# Mega_setup.net
KiCad netlist of a schematic drawn in EAGLE
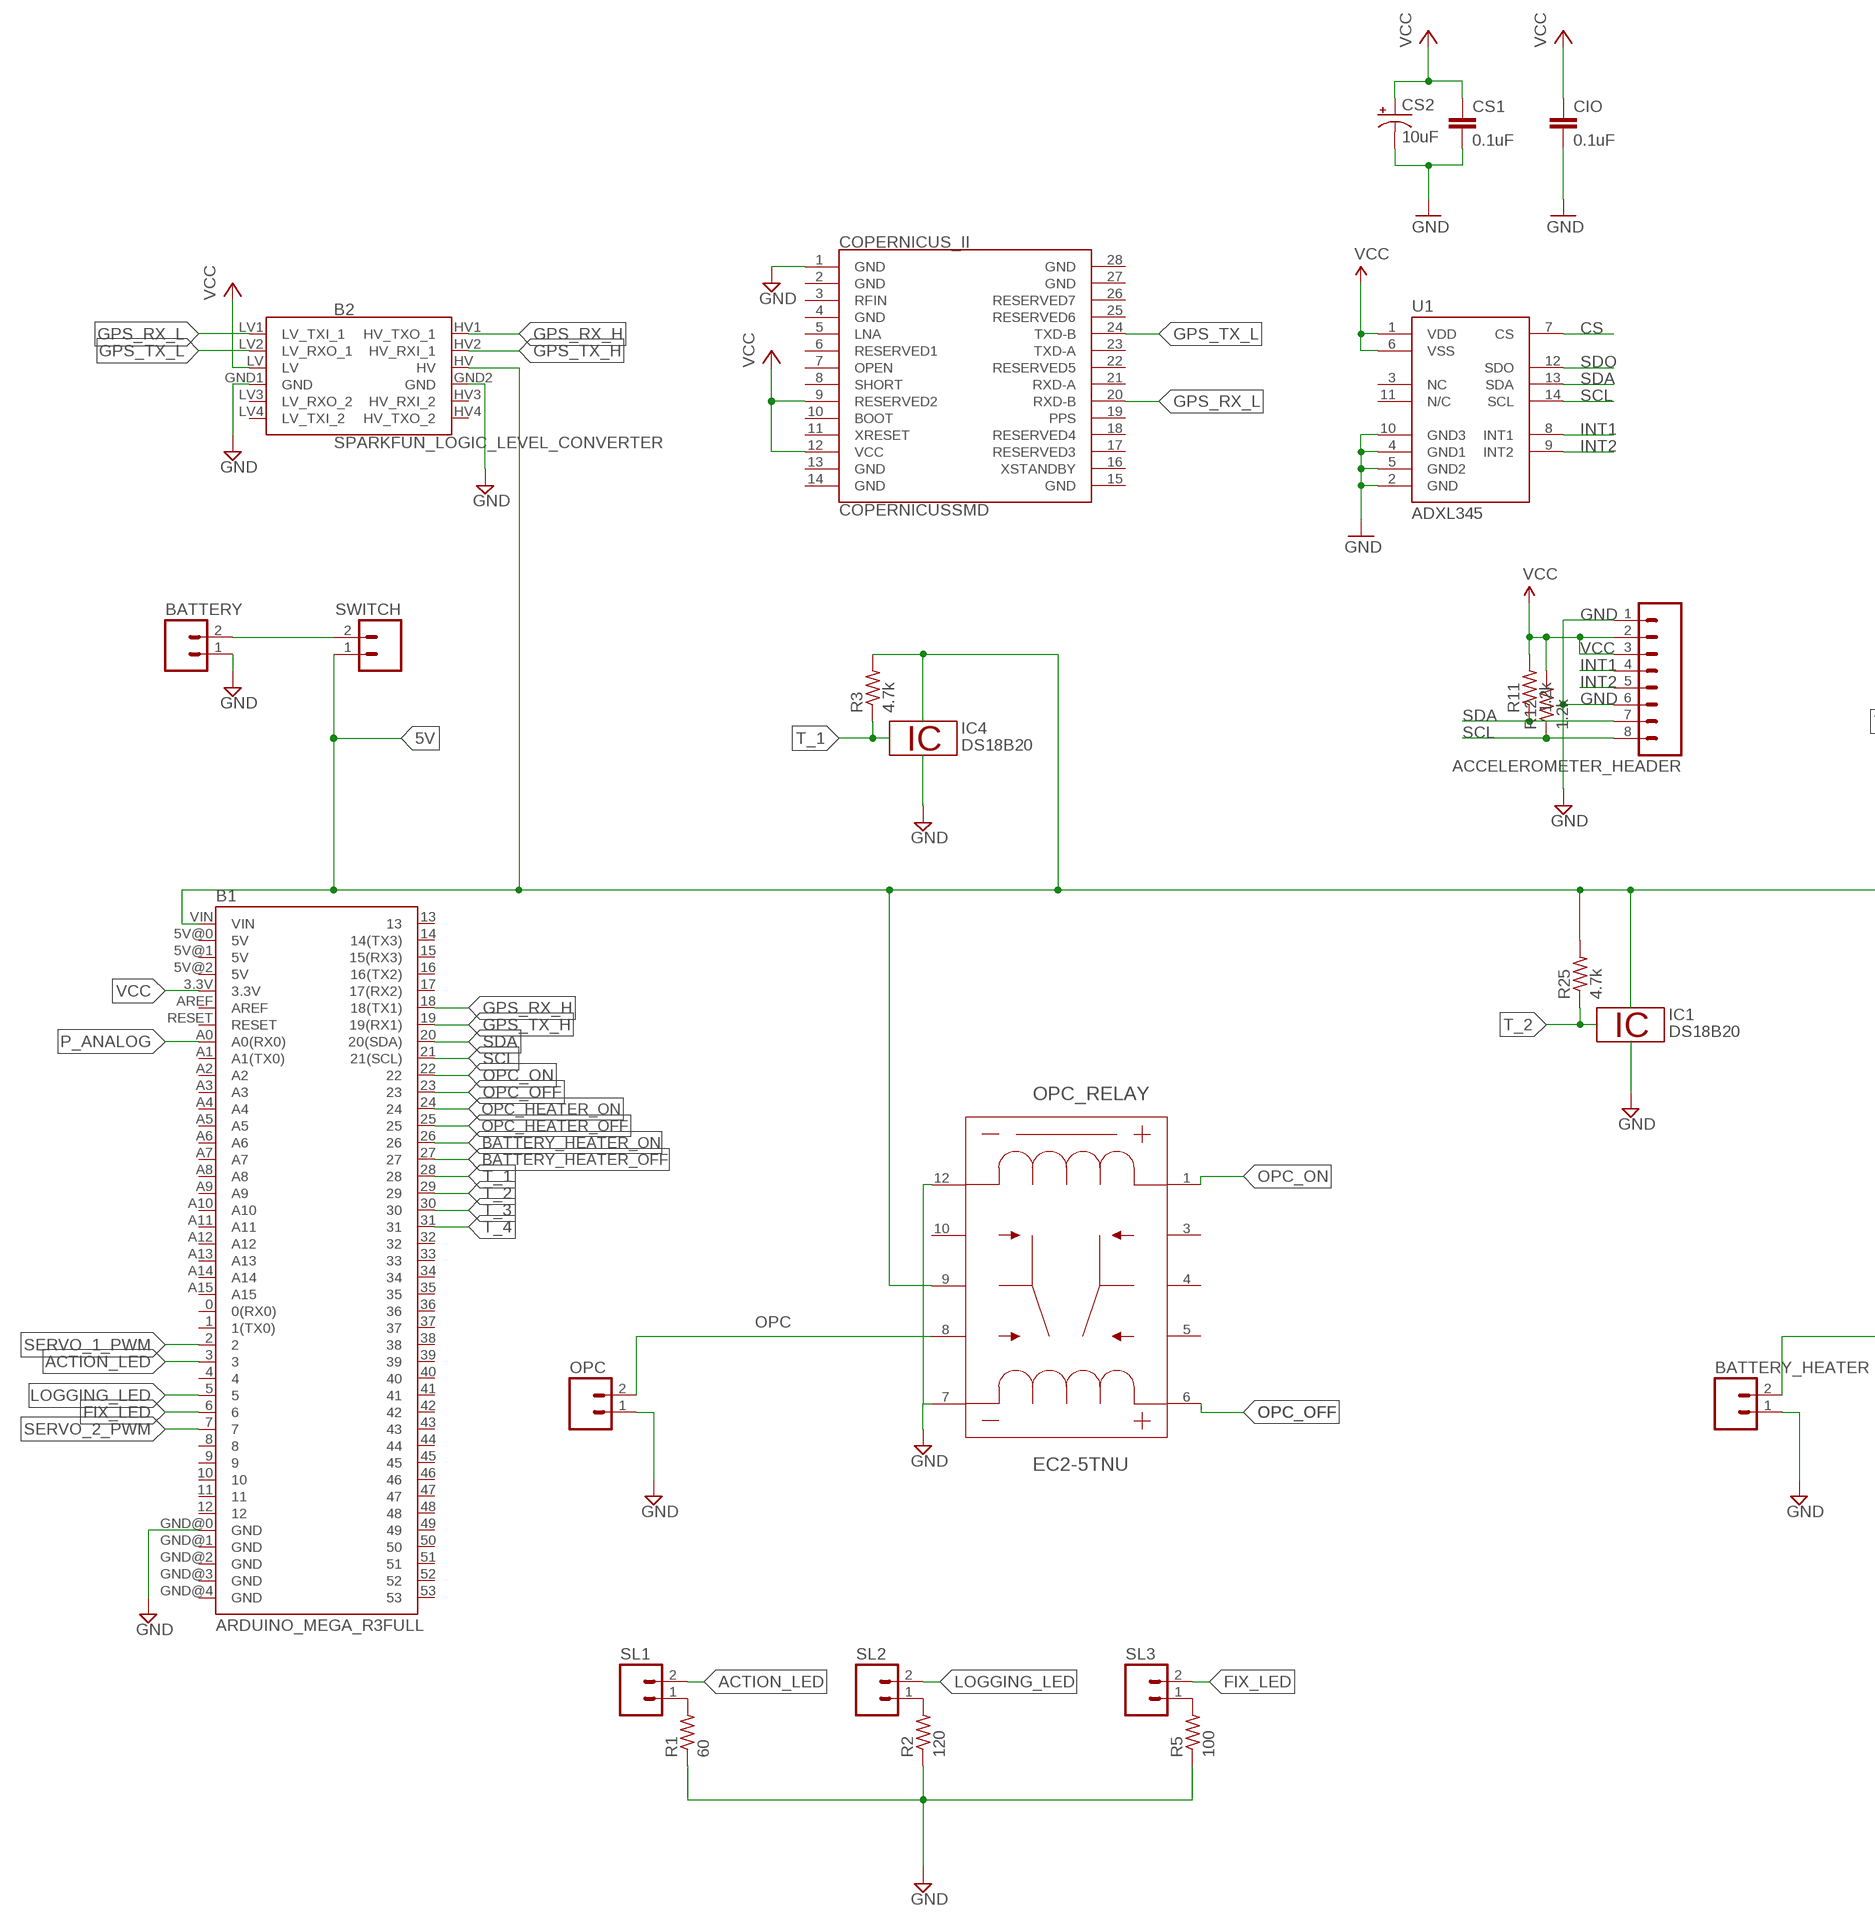
[diagram p0: schematic, sheet 1, part 1 of 2]
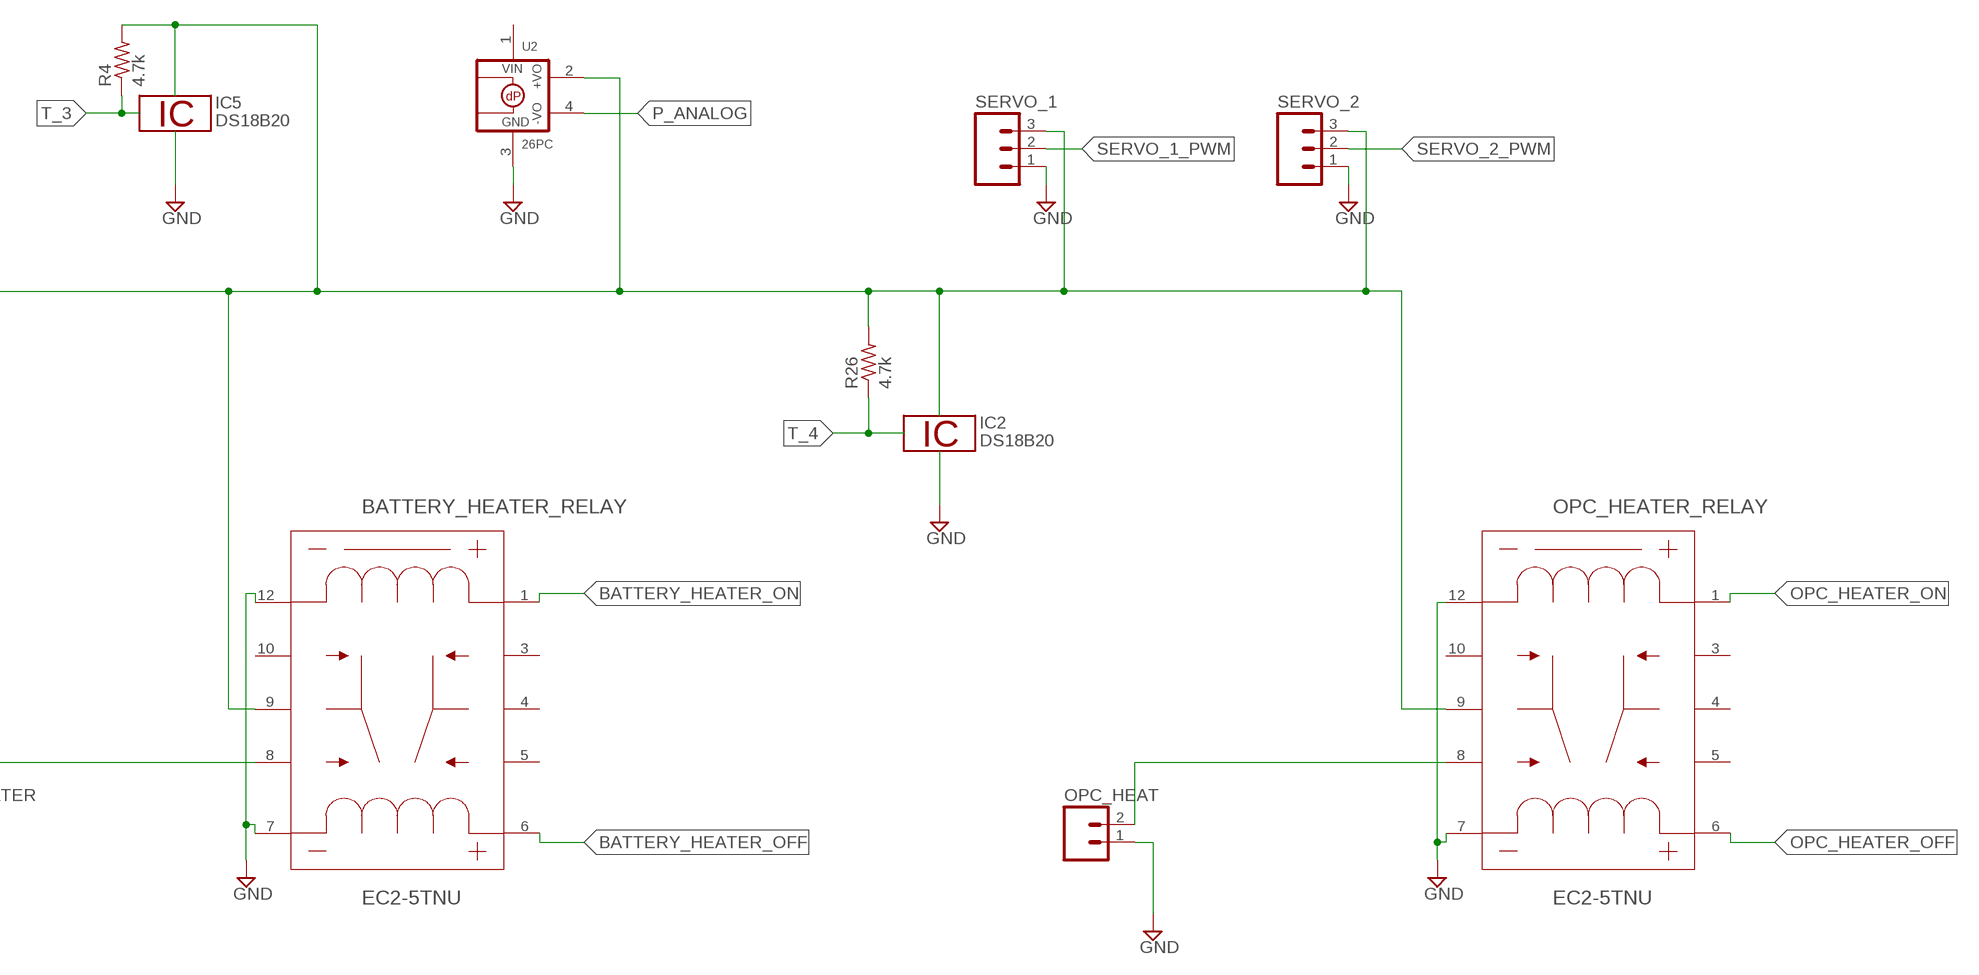
[diagram p1: schematic, sheet 1, part 2 of 2]

(export (version "E")
  (design (tool "Eeschema 10.0.6"))
  (components
    (comp (ref "ACCELEROMETER_HEADER")
      (value "M08")
      (footprint "eagle-import:1X08")
      (libsource (lib "eagle-import") (part "M08"))
    )
    (comp (ref "B1")
      (value "ARDUINO_MEGA_R3FULL")
      (footprint "eagle-import:ARDUINO_MEGA")
      (libsource (lib "eagle-import") (part "ARDUINO_MEGA_R3FULL"))
    )
    (comp (ref "B2")
      (value "SPARKFUN_LOGIC_LEVEL_CONVERTER")
      (footprint "eagle-import:SPARKFUN_LOGIC_LEVEL_CONVERTER")
      (libsource (lib "eagle-import") (part "SPARKFUN_LOGIC_LEVEL_CONVERTER"))
    )
    (comp (ref "BATTERY")
      (value "M02")
      (footprint "eagle-import:02P")
      (libsource (lib "eagle-import") (part "M02"))
    )
    (comp (ref "BATTERY_HEATER")
      (value "M02")
      (footprint "eagle-import:02P")
      (libsource (lib "eagle-import") (part "M02"))
    )
    (comp (ref "BATTERY_HEATER_RELAY")
      (value "EC2-5TNU")
      (footprint "eagle-import:EC2TNU")
      (fields (field (name "MANUFACTURER_PART_NUMBER") "EC25TNU"))
      (libsource (lib "eagle-import") (part "EC2-5TNU"))
    )
    (comp (ref "CIO")
      (value "0.1uF")
      (footprint "eagle-import:0402-CAP")
      (libsource (lib "eagle-import") (part "CAP0402-CAP"))
    )
    (comp (ref "COPERNICUS_II")
      (value "COPERNICUSSMD")
      (footprint "eagle-import:COPERNICUS")
      (libsource (lib "eagle-import") (part "COPERNICUSSMD"))
    )
    (comp (ref "CS1")
      (value "0.1uF")
      (footprint "eagle-import:0402-CAP")
      (libsource (lib "eagle-import") (part "CAP0402-CAP"))
    )
    (comp (ref "CS2")
      (value "10uF")
      (footprint "eagle-import:EIA3216")
      (libsource (lib "eagle-import") (part "CAP_POL1206"))
    )
    (comp (ref "IC1")
      (value "DS18B20")
      (footprint "eagle-import:TO92-")
      (libsource (lib "eagle-import") (part "DS18B20"))
    )
    (comp (ref "IC2")
      (value "DS18B20")
      (footprint "eagle-import:TO92-")
      (libsource (lib "eagle-import") (part "DS18B20"))
    )
    (comp (ref "IC4")
      (value "DS18B20")
      (footprint "eagle-import:TO92-")
      (libsource (lib "eagle-import") (part "DS18B20"))
    )
    (comp (ref "IC5")
      (value "DS18B20")
      (footprint "eagle-import:TO92-")
      (libsource (lib "eagle-import") (part "DS18B20"))
    )
    (comp (ref "OPC")
      (value "M02")
      (footprint "eagle-import:02P")
      (libsource (lib "eagle-import") (part "M02"))
    )
    (comp (ref "OPC_HEAT")
      (value "M02")
      (footprint "eagle-import:02P")
      (libsource (lib "eagle-import") (part "M02"))
    )
    (comp (ref "OPC_HEATER_RELAY")
      (value "EC2-5TNU")
      (footprint "eagle-import:EC2TNU")
      (fields (field (name "MANUFACTURER_PART_NUMBER") "EC25TNU"))
      (libsource (lib "eagle-import") (part "EC2-5TNU"))
    )
    (comp (ref "OPC_RELAY")
      (value "EC2-5TNU")
      (footprint "eagle-import:EC2TNU")
      (fields (field (name "MANUFACTURER_PART_NUMBER") "EC25TNU"))
      (libsource (lib "eagle-import") (part "EC2-5TNU"))
    )
    (comp (ref "R1")
      (value "60")
      (footprint "eagle-import:0204_7")
      (libsource (lib "eagle-import") (part "R-US_0204/7"))
    )
    (comp (ref "R2")
      (value "120")
      (footprint "eagle-import:0204_7")
      (libsource (lib "eagle-import") (part "R-US_0204/7"))
    )
    (comp (ref "R3")
      (value "4.7k")
      (footprint "eagle-import:0204_7")
      (libsource (lib "eagle-import") (part "R-US_0204/7"))
    )
    (comp (ref "R4")
      (value "4.7k")
      (footprint "eagle-import:0204_7")
      (libsource (lib "eagle-import") (part "R-US_0204/7"))
    )
    (comp (ref "R5")
      (value "100")
      (footprint "eagle-import:0204_7")
      (libsource (lib "eagle-import") (part "R-US_0204/7"))
    )
    (comp (ref "R11")
      (value "1.2k")
      (footprint "eagle-import:0204_7")
      (libsource (lib "eagle-import") (part "R-US_0204/7"))
    )
    (comp (ref "R12")
      (value "1.2k")
      (footprint "eagle-import:0204_7")
      (libsource (lib "eagle-import") (part "R-US_0204/7"))
    )
    (comp (ref "R25")
      (value "4.7k")
      (footprint "eagle-import:0204_7")
      (libsource (lib "eagle-import") (part "R-US_0204/7"))
    )
    (comp (ref "R26")
      (value "4.7k")
      (footprint "eagle-import:0204_7")
      (libsource (lib "eagle-import") (part "R-US_0204/7"))
    )
    (comp (ref "SERVO_1")
      (value "M03")
      (footprint "eagle-import:03P")
      (libsource (lib "eagle-import") (part "M03"))
    )
    (comp (ref "SERVO_2")
      (value "M03")
      (footprint "eagle-import:03P")
      (libsource (lib "eagle-import") (part "M03"))
    )
    (comp (ref "SL1")
      (value "M02")
      (footprint "eagle-import:02P")
      (libsource (lib "eagle-import") (part "M02"))
    )
    (comp (ref "SL2")
      (value "M02")
      (footprint "eagle-import:02P")
      (libsource (lib "eagle-import") (part "M02"))
    )
    (comp (ref "SL3")
      (value "M02")
      (footprint "eagle-import:02P")
      (libsource (lib "eagle-import") (part "M02"))
    )
    (comp (ref "SWITCH")
      (value "M02")
      (footprint "eagle-import:02P")
      (libsource (lib "eagle-import") (part "M02"))
    )
    (comp (ref "U1")
      (value "ADXL345")
      (footprint "eagle-import:LGA14")
      (libsource (lib "eagle-import") (part "ADXL345"))
    )
    (comp (ref "U2")
      (value "26PC")
      (footprint "eagle-import:26PC")
      (libsource (lib "eagle-import") (part "26PC"))
    )
  )
  (nets
    (net (code "1") (name "/CS") (class "Default")
      (node (ref "U1") (pin "7") (pinfunction "CS_7") (pintype "bidirectional"))
    )
    (net (code "2") (name "/INT1") (class "Default")
      (node (ref "ACCELEROMETER_HEADER") (pin "4") (pinfunction "4_4") (pintype "passive"))
      (node (ref "U1") (pin "8") (pinfunction "INT1_8") (pintype "bidirectional"))
    )
    (net (code "3") (name "/INT2") (class "Default")
      (node (ref "ACCELEROMETER_HEADER") (pin "5") (pinfunction "5_5") (pintype "passive"))
      (node (ref "U1") (pin "9") (pinfunction "INT2_9") (pintype "bidirectional"))
    )
    (net (code "4") (name "/OPC") (class "Default")
      (node (ref "BATTERY_HEATER") (pin "2") (pinfunction "2_2") (pintype "passive"))
      (node (ref "BATTERY_HEATER_RELAY") (pin "8") (pinfunction "7_8") (pintype "passive"))
      (node (ref "OPC") (pin "2") (pinfunction "2_2") (pintype "passive"))
      (node (ref "OPC_RELAY") (pin "8") (pinfunction "7_8") (pintype "passive"))
    )
    (net (code "5") (name "/SDO") (class "Default")
      (node (ref "U1") (pin "12") (pinfunction "SDO_12") (pintype "bidirectional"))
    )
    (net (code "6") (name "/VIN") (class "Default")
      (node (ref "U2") (pin "1") (pinfunction "VIN_1") (pintype "power_in"))
    )
    (net (code "7") (name "5V") (class "Default")
      (node (ref "B1") (pin "VIN") (pinfunction "VIN_VIN") (pintype "bidirectional"))
      (node (ref "B2") (pin "HV") (pinfunction "HV_HV") (pintype "power_in"))
      (node (ref "BATTERY_HEATER_RELAY") (pin "9") (pinfunction "8_9") (pintype "passive"))
      (node (ref "OPC_HEATER_RELAY") (pin "9") (pinfunction "8_9") (pintype "passive"))
      (node (ref "OPC_RELAY") (pin "9") (pinfunction "8_9") (pintype "passive"))
      (node (ref "R25") (pin "2") (pinfunction "2_2") (pintype "passive"))
      (node (ref "R26") (pin "2") (pinfunction "2_2") (pintype "passive"))
      (node (ref "R3") (pin "2") (pinfunction "2_2") (pintype "passive"))
      (node (ref "R4") (pin "2") (pinfunction "2_2") (pintype "passive"))
      (node (ref "SERVO_1") (pin "3") (pinfunction "3_3") (pintype "passive"))
      (node (ref "SERVO_2") (pin "3") (pinfunction "3_3") (pintype "passive"))
      (node (ref "SWITCH") (pin "1") (pinfunction "1_1") (pintype "passive"))
      (node (ref "U2") (pin "2") (pinfunction "OUT+_2") (pintype "output"))
    )
    (net (code "8") (name "ACTION_LED") (class "Default")
      (node (ref "B1") (pin "3") (pinfunction "3_3") (pintype "bidirectional"))
      (node (ref "SL1") (pin "2") (pinfunction "2_2") (pintype "passive"))
    )
    (net (code "9") (name "BATTERY_HEATER_OFF") (class "Default")
      (node (ref "B1") (pin "27") (pinfunction "27_27") (pintype "bidirectional"))
      (node (ref "BATTERY_HEATER_RELAY") (pin "6") (pinfunction "5_6") (pintype "passive"))
    )
    (net (code "10") (name "BATTERY_HEATER_ON") (class "Default")
      (node (ref "B1") (pin "26") (pinfunction "26_26") (pintype "bidirectional"))
      (node (ref "BATTERY_HEATER_RELAY") (pin "1") (pinfunction "1_1") (pintype "passive"))
    )
    (net (code "11") (name "FIX_LED") (class "Default")
      (node (ref "B1") (pin "6") (pinfunction "6_6") (pintype "bidirectional"))
      (node (ref "SL3") (pin "2") (pinfunction "2_2") (pintype "passive"))
    )
    (net (code "12") (name "GND") (class "Default")
      (node (ref "ACCELEROMETER_HEADER") (pin "1") (pinfunction "1_1") (pintype "passive"))
      (node (ref "ACCELEROMETER_HEADER") (pin "6") (pinfunction "6_6") (pintype "passive"))
      (node (ref "B1") (pin "GND@0") (pinfunction "GND_GND@0") (pintype "bidirectional"))
      (node (ref "B2") (pin "GND1") (pinfunction "GND_GND1") (pintype "power_in"))
      (node (ref "B2") (pin "GND2") (pinfunction "GND_GND2") (pintype "power_in"))
      (node (ref "BATTERY") (pin "1") (pinfunction "1_1") (pintype "passive"))
      (node (ref "BATTERY_HEATER") (pin "1") (pinfunction "1_1") (pintype "passive"))
      (node (ref "BATTERY_HEATER_RELAY") (pin "12") (pinfunction "10_12") (pintype "passive"))
      (node (ref "BATTERY_HEATER_RELAY") (pin "7") (pinfunction "6_7") (pintype "passive"))
      (node (ref "CIO") (pin "2") (pinfunction "2_2") (pintype "passive"))
      (node (ref "COPERNICUS_II") (pin "1") (pinfunction "GND_1") (pintype "bidirectional"))
      (node (ref "CS1") (pin "2") (pinfunction "2_2") (pintype "passive"))
      (node (ref "CS2") (pin "C") (pinfunction "-_C") (pintype "passive"))
      (node (ref "OPC") (pin "1") (pinfunction "1_1") (pintype "passive"))
      (node (ref "OPC_HEAT") (pin "1") (pinfunction "1_1") (pintype "passive"))
      (node (ref "OPC_HEATER_RELAY") (pin "12") (pinfunction "10_12") (pintype "passive"))
      (node (ref "OPC_HEATER_RELAY") (pin "7") (pinfunction "6_7") (pintype "passive"))
      (node (ref "OPC_RELAY") (pin "12") (pinfunction "10_12") (pintype "passive"))
      (node (ref "OPC_RELAY") (pin "7") (pinfunction "6_7") (pintype "passive"))
      (node (ref "R1") (pin "1") (pinfunction "1_1") (pintype "passive"))
      (node (ref "R2") (pin "1") (pinfunction "1_1") (pintype "passive"))
      (node (ref "R5") (pin "1") (pinfunction "1_1") (pintype "passive"))
      (node (ref "SERVO_1") (pin "1") (pinfunction "1_1") (pintype "passive"))
      (node (ref "SERVO_2") (pin "1") (pinfunction "1_1") (pintype "passive"))
      (node (ref "U1") (pin "10") (pinfunction "GND3_10") (pintype "bidirectional"))
      (node (ref "U1") (pin "2") (pinfunction "GND_2") (pintype "bidirectional"))
      (node (ref "U1") (pin "4") (pinfunction "GND1_4") (pintype "bidirectional"))
      (node (ref "U1") (pin "5") (pinfunction "GND2_5") (pintype "bidirectional"))
      (node (ref "U2") (pin "3") (pinfunction "GND_3") (pintype "power_in"))
    )
    (net (code "13") (name "GPS_RX_H") (class "Default")
      (node (ref "B1") (pin "18") (pinfunction "18(TX1)_18") (pintype "bidirectional"))
      (node (ref "B2") (pin "HV1") (pinfunction "HV_TXO_1_HV1") (pintype "bidirectional"))
    )
    (net (code "14") (name "GPS_RX_L") (class "Default")
      (node (ref "B2") (pin "LV1") (pinfunction "LV_TXI_1_LV1") (pintype "bidirectional"))
      (node (ref "COPERNICUS_II") (pin "20") (pinfunction "RXD-B_20") (pintype "bidirectional"))
    )
    (net (code "15") (name "GPS_TX_H") (class "Default")
      (node (ref "B1") (pin "19") (pinfunction "19(RX1)_19") (pintype "bidirectional"))
      (node (ref "B2") (pin "HV2") (pinfunction "HV_RXI_1_HV2") (pintype "bidirectional"))
    )
    (net (code "16") (name "GPS_TX_L") (class "Default")
      (node (ref "B2") (pin "LV2") (pinfunction "LV_RXO_1_LV2") (pintype "bidirectional"))
      (node (ref "COPERNICUS_II") (pin "24") (pinfunction "TXD-B_24") (pintype "bidirectional"))
    )
    (net (code "17") (name "LOGGING_LED") (class "Default")
      (node (ref "B1") (pin "5") (pinfunction "5_5") (pintype "bidirectional"))
      (node (ref "SL2") (pin "2") (pinfunction "2_2") (pintype "passive"))
    )
    (net (code "18") (name "Net-(BATTERY-Pad2)") (class "Default")
      (node (ref "BATTERY") (pin "2") (pinfunction "2_2") (pintype "passive"))
      (node (ref "SWITCH") (pin "2") (pinfunction "2_2") (pintype "passive"))
    )
    (net (code "19") (name "Net-(OPC_HEATER_RELAY-7)") (class "Default")
      (node (ref "OPC_HEAT") (pin "2") (pinfunction "2_2") (pintype "passive"))
      (node (ref "OPC_HEATER_RELAY") (pin "8") (pinfunction "7_8") (pintype "passive"))
    )
    (net (code "20") (name "Net-(R1-Pad2)") (class "Default")
      (node (ref "R1") (pin "2") (pinfunction "2_2") (pintype "passive"))
      (node (ref "SL1") (pin "1") (pinfunction "1_1") (pintype "passive"))
    )
    (net (code "21") (name "Net-(R2-Pad2)") (class "Default")
      (node (ref "R2") (pin "2") (pinfunction "2_2") (pintype "passive"))
      (node (ref "SL2") (pin "1") (pinfunction "1_1") (pintype "passive"))
    )
    (net (code "22") (name "Net-(R5-Pad2)") (class "Default")
      (node (ref "R5") (pin "2") (pinfunction "2_2") (pintype "passive"))
      (node (ref "SL3") (pin "1") (pinfunction "1_1") (pintype "passive"))
    )
    (net (code "23") (name "OPC_HEATER_OFF") (class "Default")
      (node (ref "B1") (pin "25") (pinfunction "25_25") (pintype "bidirectional"))
      (node (ref "OPC_HEATER_RELAY") (pin "6") (pinfunction "5_6") (pintype "passive"))
    )
    (net (code "24") (name "OPC_HEATER_ON") (class "Default")
      (node (ref "B1") (pin "24") (pinfunction "24_24") (pintype "bidirectional"))
      (node (ref "OPC_HEATER_RELAY") (pin "1") (pinfunction "1_1") (pintype "passive"))
    )
    (net (code "25") (name "OPC_OFF") (class "Default")
      (node (ref "B1") (pin "23") (pinfunction "23_23") (pintype "bidirectional"))
      (node (ref "OPC_RELAY") (pin "6") (pinfunction "5_6") (pintype "passive"))
    )
    (net (code "26") (name "OPC_ON") (class "Default")
      (node (ref "B1") (pin "22") (pinfunction "22_22") (pintype "bidirectional"))
      (node (ref "OPC_RELAY") (pin "1") (pinfunction "1_1") (pintype "passive"))
    )
    (net (code "27") (name "P_ANALOG") (class "Default")
      (node (ref "B1") (pin "A0") (pinfunction "A0(RX0)_A0") (pintype "bidirectional"))
      (node (ref "U2") (pin "4") (pinfunction "OUT-_4") (pintype "output"))
    )
    (net (code "28") (name "SCL") (class "Default")
      (node (ref "ACCELEROMETER_HEADER") (pin "8") (pinfunction "8_8") (pintype "passive"))
      (node (ref "B1") (pin "21") (pinfunction "21(SCL)_21") (pintype "bidirectional"))
      (node (ref "R12") (pin "1") (pinfunction "1_1") (pintype "passive"))
      (node (ref "U1") (pin "14") (pinfunction "SCL_14") (pintype "bidirectional"))
    )
    (net (code "29") (name "SDA") (class "Default")
      (node (ref "ACCELEROMETER_HEADER") (pin "7") (pinfunction "7_7") (pintype "passive"))
      (node (ref "B1") (pin "20") (pinfunction "20(SDA)_20") (pintype "bidirectional"))
      (node (ref "R11") (pin "1") (pinfunction "1_1") (pintype "passive"))
      (node (ref "U1") (pin "13") (pinfunction "SDA_13") (pintype "bidirectional"))
    )
    (net (code "30") (name "SERVO_1_PWM") (class "Default")
      (node (ref "B1") (pin "2") (pinfunction "2_2") (pintype "bidirectional"))
      (node (ref "SERVO_1") (pin "2") (pinfunction "2_2") (pintype "passive"))
    )
    (net (code "31") (name "SERVO_2_PWM") (class "Default")
      (node (ref "B1") (pin "7") (pinfunction "7_7") (pintype "bidirectional"))
      (node (ref "SERVO_2") (pin "2") (pinfunction "2_2") (pintype "passive"))
    )
    (net (code "32") (name "T_1") (class "Default")
      (node (ref "B1") (pin "28") (pinfunction "28_28") (pintype "bidirectional"))
      (node (ref "R3") (pin "1") (pinfunction "1_1") (pintype "passive"))
    )
    (net (code "33") (name "T_2") (class "Default")
      (node (ref "B1") (pin "29") (pinfunction "29_29") (pintype "bidirectional"))
      (node (ref "R25") (pin "1") (pinfunction "1_1") (pintype "passive"))
    )
    (net (code "34") (name "T_3") (class "Default")
      (node (ref "B1") (pin "30") (pinfunction "30_30") (pintype "bidirectional"))
      (node (ref "R4") (pin "1") (pinfunction "1_1") (pintype "passive"))
    )
    (net (code "35") (name "T_4") (class "Default")
      (node (ref "B1") (pin "31") (pinfunction "31_31") (pintype "bidirectional"))
      (node (ref "R26") (pin "1") (pinfunction "1_1") (pintype "passive"))
    )
    (net (code "36") (name "VCC") (class "Default")
      (node (ref "ACCELEROMETER_HEADER") (pin "2") (pinfunction "2_2") (pintype "passive"))
      (node (ref "ACCELEROMETER_HEADER") (pin "3") (pinfunction "3_3") (pintype "passive"))
      (node (ref "B1") (pin "3.3V") (pinfunction "3.3V_3.3V") (pintype "bidirectional"))
      (node (ref "B2") (pin "LV") (pinfunction "LV_LV") (pintype "power_in"))
      (node (ref "CIO") (pin "1") (pinfunction "1_1") (pintype "passive"))
      (node (ref "COPERNICUS_II") (pin "12") (pinfunction "VCC_12") (pintype "bidirectional"))
      (node (ref "COPERNICUS_II") (pin "9") (pinfunction "RESERVED2_9") (pintype "bidirectional"))
      (node (ref "CS1") (pin "1") (pinfunction "1_1") (pintype "passive"))
      (node (ref "CS2") (pin "A") (pinfunction "+_A") (pintype "passive"))
      (node (ref "R11") (pin "2") (pinfunction "2_2") (pintype "passive"))
      (node (ref "R12") (pin "2") (pinfunction "2_2") (pintype "passive"))
      (node (ref "U1") (pin "1") (pinfunction "VDD_1") (pintype "bidirectional"))
      (node (ref "U1") (pin "6") (pinfunction "VSS_6") (pintype "bidirectional"))
    )
    (net (code "37") (name "unconnected-(B1-0(RX0)-Pad0)") (class "Default")
      (node (ref "B1") (pin "0") (pinfunction "0(RX0)_0") (pintype "bidirectional"))
    )
    (net (code "38") (name "unconnected-(B1-1(TX0)-Pad1)") (class "Default")
      (node (ref "B1") (pin "1") (pinfunction "1(TX0)_1") (pintype "bidirectional"))
    )
    (net (code "39") (name "unconnected-(B1-5V-Pad5V@0)") (class "Default")
      (node (ref "B1") (pin "5V@0") (pinfunction "5V_5V@0") (pintype "bidirectional"))
    )
    (net (code "40") (name "unconnected-(B1-5V-Pad5V@1)") (class "Default")
      (node (ref "B1") (pin "5V@1") (pinfunction "5V_5V@1") (pintype "bidirectional"))
    )
    (net (code "41") (name "unconnected-(B1-5V-Pad5V@2)") (class "Default")
      (node (ref "B1") (pin "5V@2") (pinfunction "5V_5V@2") (pintype "bidirectional"))
    )
    (net (code "42") (name "unconnected-(B1-14(TX3)-Pad14)") (class "Default")
      (node (ref "B1") (pin "14") (pinfunction "14(TX3)_14") (pintype "bidirectional"))
    )
    (net (code "43") (name "unconnected-(B1-15(RX3)-Pad15)") (class "Default")
      (node (ref "B1") (pin "15") (pinfunction "15(RX3)_15") (pintype "bidirectional"))
    )
    (net (code "44") (name "unconnected-(B1-16(TX2)-Pad16)") (class "Default")
      (node (ref "B1") (pin "16") (pinfunction "16(TX2)_16") (pintype "bidirectional"))
    )
    (net (code "45") (name "unconnected-(B1-17(RX2)-Pad17)") (class "Default")
      (node (ref "B1") (pin "17") (pinfunction "17(RX2)_17") (pintype "bidirectional"))
    )
    (net (code "46") (name "unconnected-(B1-A1(TX0)-PadA1)") (class "Default")
      (node (ref "B1") (pin "A1") (pinfunction "A1(TX0)_A1") (pintype "bidirectional"))
    )
    (net (code "47") (name "unconnected-(B1-GND-PadGND@1)") (class "Default")
      (node (ref "B1") (pin "GND@1") (pinfunction "GND_GND@1") (pintype "bidirectional"))
    )
    (net (code "48") (name "unconnected-(B1-GND-PadGND@2)") (class "Default")
      (node (ref "B1") (pin "GND@2") (pinfunction "GND_GND@2") (pintype "bidirectional"))
    )
    (net (code "49") (name "unconnected-(B1-GND-PadGND@3)") (class "Default")
      (node (ref "B1") (pin "GND@3") (pinfunction "GND_GND@3") (pintype "bidirectional"))
    )
    (net (code "50") (name "unconnected-(B1-GND-PadGND@4)") (class "Default")
      (node (ref "B1") (pin "GND@4") (pinfunction "GND_GND@4") (pintype "bidirectional"))
    )
    (net (code "51") (name "unconnected-(B1-Pad4)") (class "Default")
      (node (ref "B1") (pin "4") (pinfunction "4_4") (pintype "bidirectional"))
    )
    (net (code "52") (name "unconnected-(B1-Pad8)") (class "Default")
      (node (ref "B1") (pin "8") (pinfunction "8_8") (pintype "bidirectional"))
    )
    (net (code "53") (name "unconnected-(B1-Pad9)") (class "Default")
      (node (ref "B1") (pin "9") (pinfunction "9_9") (pintype "bidirectional"))
    )
    (net (code "54") (name "unconnected-(B1-Pad10)") (class "Default")
      (node (ref "B1") (pin "10") (pinfunction "10_10") (pintype "bidirectional"))
    )
    (net (code "55") (name "unconnected-(B1-Pad11)") (class "Default")
      (node (ref "B1") (pin "11") (pinfunction "11_11") (pintype "bidirectional"))
    )
    (net (code "56") (name "unconnected-(B1-Pad12)") (class "Default")
      (node (ref "B1") (pin "12") (pinfunction "12_12") (pintype "bidirectional"))
    )
    (net (code "57") (name "unconnected-(B1-Pad13)") (class "Default")
      (node (ref "B1") (pin "13") (pinfunction "13_13") (pintype "bidirectional"))
    )
    (net (code "58") (name "unconnected-(B1-Pad32)") (class "Default")
      (node (ref "B1") (pin "32") (pinfunction "32_32") (pintype "bidirectional"))
    )
    (net (code "59") (name "unconnected-(B1-Pad33)") (class "Default")
      (node (ref "B1") (pin "33") (pinfunction "33_33") (pintype "bidirectional"))
    )
    (net (code "60") (name "unconnected-(B1-Pad34)") (class "Default")
      (node (ref "B1") (pin "34") (pinfunction "34_34") (pintype "bidirectional"))
    )
    (net (code "61") (name "unconnected-(B1-Pad35)") (class "Default")
      (node (ref "B1") (pin "35") (pinfunction "35_35") (pintype "bidirectional"))
    )
    (net (code "62") (name "unconnected-(B1-Pad36)") (class "Default")
      (node (ref "B1") (pin "36") (pinfunction "36_36") (pintype "bidirectional"))
    )
    (net (code "63") (name "unconnected-(B1-Pad37)") (class "Default")
      (node (ref "B1") (pin "37") (pinfunction "37_37") (pintype "bidirectional"))
    )
    (net (code "64") (name "unconnected-(B1-Pad38)") (class "Default")
      (node (ref "B1") (pin "38") (pinfunction "38_38") (pintype "bidirectional"))
    )
    (net (code "65") (name "unconnected-(B1-Pad39)") (class "Default")
      (node (ref "B1") (pin "39") (pinfunction "39_39") (pintype "bidirectional"))
    )
    (net (code "66") (name "unconnected-(B1-Pad40)") (class "Default")
      (node (ref "B1") (pin "40") (pinfunction "40_40") (pintype "bidirectional"))
    )
    (net (code "67") (name "unconnected-(B1-Pad41)") (class "Default")
      (node (ref "B1") (pin "41") (pinfunction "41_41") (pintype "bidirectional"))
    )
    (net (code "68") (name "unconnected-(B1-Pad42)") (class "Default")
      (node (ref "B1") (pin "42") (pinfunction "42_42") (pintype "bidirectional"))
    )
    (net (code "69") (name "unconnected-(B1-Pad43)") (class "Default")
      (node (ref "B1") (pin "43") (pinfunction "43_43") (pintype "bidirectional"))
    )
    (net (code "70") (name "unconnected-(B1-Pad44)") (class "Default")
      (node (ref "B1") (pin "44") (pinfunction "44_44") (pintype "bidirectional"))
    )
    (net (code "71") (name "unconnected-(B1-Pad45)") (class "Default")
      (node (ref "B1") (pin "45") (pinfunction "45_45") (pintype "bidirectional"))
    )
    (net (code "72") (name "unconnected-(B1-Pad46)") (class "Default")
      (node (ref "B1") (pin "46") (pinfunction "46_46") (pintype "bidirectional"))
    )
    (net (code "73") (name "unconnected-(B1-Pad47)") (class "Default")
      (node (ref "B1") (pin "47") (pinfunction "47_47") (pintype "bidirectional"))
    )
    (net (code "74") (name "unconnected-(B1-Pad48)") (class "Default")
      (node (ref "B1") (pin "48") (pinfunction "48_48") (pintype "bidirectional"))
    )
    (net (code "75") (name "unconnected-(B1-Pad49)") (class "Default")
      (node (ref "B1") (pin "49") (pinfunction "49_49") (pintype "bidirectional"))
    )
    (net (code "76") (name "unconnected-(B1-Pad50)") (class "Default")
      (node (ref "B1") (pin "50") (pinfunction "50_50") (pintype "bidirectional"))
    )
    (net (code "77") (name "unconnected-(B1-Pad51)") (class "Default")
      (node (ref "B1") (pin "51") (pinfunction "51_51") (pintype "bidirectional"))
    )
    (net (code "78") (name "unconnected-(B1-Pad52)") (class "Default")
      (node (ref "B1") (pin "52") (pinfunction "52_52") (pintype "bidirectional"))
    )
    (net (code "79") (name "unconnected-(B1-Pad53)") (class "Default")
      (node (ref "B1") (pin "53") (pinfunction "53_53") (pintype "bidirectional"))
    )
    (net (code "80") (name "unconnected-(B1-PadA2)") (class "Default")
      (node (ref "B1") (pin "A2") (pinfunction "A2_A2") (pintype "bidirectional"))
    )
    (net (code "81") (name "unconnected-(B1-PadA3)") (class "Default")
      (node (ref "B1") (pin "A3") (pinfunction "A3_A3") (pintype "bidirectional"))
    )
    (net (code "82") (name "unconnected-(B1-PadA4)") (class "Default")
      (node (ref "B1") (pin "A4") (pinfunction "A4_A4") (pintype "bidirectional"))
    )
    (net (code "83") (name "unconnected-(B1-PadA5)") (class "Default")
      (node (ref "B1") (pin "A5") (pinfunction "A5_A5") (pintype "bidirectional"))
    )
    (net (code "84") (name "unconnected-(B1-PadA6)") (class "Default")
      (node (ref "B1") (pin "A6") (pinfunction "A6_A6") (pintype "bidirectional"))
    )
    (net (code "85") (name "unconnected-(B1-PadA7)") (class "Default")
      (node (ref "B1") (pin "A7") (pinfunction "A7_A7") (pintype "bidirectional"))
    )
    (net (code "86") (name "unconnected-(B1-PadA8)") (class "Default")
      (node (ref "B1") (pin "A8") (pinfunction "A8_A8") (pintype "bidirectional"))
    )
    (net (code "87") (name "unconnected-(B1-PadA9)") (class "Default")
      (node (ref "B1") (pin "A9") (pinfunction "A9_A9") (pintype "bidirectional"))
    )
    (net (code "88") (name "unconnected-(B1-PadA10)") (class "Default")
      (node (ref "B1") (pin "A10") (pinfunction "A10_A10") (pintype "bidirectional"))
    )
    (net (code "89") (name "unconnected-(B1-PadA11)") (class "Default")
      (node (ref "B1") (pin "A11") (pinfunction "A11_A11") (pintype "bidirectional"))
    )
    (net (code "90") (name "unconnected-(B1-PadA12)") (class "Default")
      (node (ref "B1") (pin "A12") (pinfunction "A12_A12") (pintype "bidirectional"))
    )
    (net (code "91") (name "unconnected-(B1-PadA13)") (class "Default")
      (node (ref "B1") (pin "A13") (pinfunction "A13_A13") (pintype "bidirectional"))
    )
    (net (code "92") (name "unconnected-(B1-PadA14)") (class "Default")
      (node (ref "B1") (pin "A14") (pinfunction "A14_A14") (pintype "bidirectional"))
    )
    (net (code "93") (name "unconnected-(B1-PadA15)") (class "Default")
      (node (ref "B1") (pin "A15") (pinfunction "A15_A15") (pintype "bidirectional"))
    )
    (net (code "94") (name "unconnected-(B1-PadAREF)") (class "Default")
      (node (ref "B1") (pin "AREF") (pinfunction "AREF_AREF") (pintype "bidirectional"))
    )
    (net (code "95") (name "unconnected-(B1-PadRESET)") (class "Default")
      (node (ref "B1") (pin "RESET") (pinfunction "RESET_RESET") (pintype "bidirectional"))
    )
    (net (code "96") (name "unconnected-(B2-HV_RXI_2-PadHV3)") (class "Default")
      (node (ref "B2") (pin "HV3") (pinfunction "HV_RXI_2_HV3") (pintype "bidirectional"))
    )
    (net (code "97") (name "unconnected-(B2-HV_TXO_2-PadHV4)") (class "Default")
      (node (ref "B2") (pin "HV4") (pinfunction "HV_TXO_2_HV4") (pintype "bidirectional"))
    )
    (net (code "98") (name "unconnected-(B2-LV_RXO_2-PadLV3)") (class "Default")
      (node (ref "B2") (pin "LV3") (pinfunction "LV_RXO_2_LV3") (pintype "bidirectional"))
    )
    (net (code "99") (name "unconnected-(B2-LV_TXI_2-PadLV4)") (class "Default")
      (node (ref "B2") (pin "LV4") (pinfunction "LV_TXI_2_LV4") (pintype "bidirectional"))
    )
    (net (code "100") (name "unconnected-(BATTERY_HEATER_RELAY-2-Pad3)") (class "Default")
      (node (ref "BATTERY_HEATER_RELAY") (pin "3") (pinfunction "2_3") (pintype "passive"))
    )
    (net (code "101") (name "unconnected-(BATTERY_HEATER_RELAY-3-Pad4)") (class "Default")
      (node (ref "BATTERY_HEATER_RELAY") (pin "4") (pinfunction "3_4") (pintype "passive"))
    )
    (net (code "102") (name "unconnected-(BATTERY_HEATER_RELAY-4-Pad5)") (class "Default")
      (node (ref "BATTERY_HEATER_RELAY") (pin "5") (pinfunction "4_5") (pintype "passive"))
    )
    (net (code "103") (name "unconnected-(BATTERY_HEATER_RELAY-9-Pad10)") (class "Default")
      (node (ref "BATTERY_HEATER_RELAY") (pin "10") (pinfunction "9_10") (pintype "passive"))
    )
    (net (code "104") (name "unconnected-(COPERNICUS_II-BOOT-Pad10)") (class "Default")
      (node (ref "COPERNICUS_II") (pin "10") (pinfunction "BOOT_10") (pintype "bidirectional"))
    )
    (net (code "105") (name "unconnected-(COPERNICUS_II-GND-Pad2)") (class "Default")
      (node (ref "COPERNICUS_II") (pin "2") (pinfunction "GND_2") (pintype "bidirectional"))
    )
    (net (code "106") (name "unconnected-(COPERNICUS_II-GND-Pad4)") (class "Default")
      (node (ref "COPERNICUS_II") (pin "4") (pinfunction "GND_4") (pintype "bidirectional"))
    )
    (net (code "107") (name "unconnected-(COPERNICUS_II-GND-Pad13)") (class "Default")
      (node (ref "COPERNICUS_II") (pin "13") (pinfunction "GND_13") (pintype "bidirectional"))
    )
    (net (code "108") (name "unconnected-(COPERNICUS_II-GND-Pad14)") (class "Default")
      (node (ref "COPERNICUS_II") (pin "14") (pinfunction "GND_14") (pintype "bidirectional"))
    )
    (net (code "109") (name "unconnected-(COPERNICUS_II-GND-Pad15)") (class "Default")
      (node (ref "COPERNICUS_II") (pin "15") (pinfunction "GND_15") (pintype "bidirectional"))
    )
    (net (code "110") (name "unconnected-(COPERNICUS_II-GND-Pad27)") (class "Default")
      (node (ref "COPERNICUS_II") (pin "27") (pinfunction "GND_27") (pintype "bidirectional"))
    )
    (net (code "111") (name "unconnected-(COPERNICUS_II-GND-Pad28)") (class "Default")
      (node (ref "COPERNICUS_II") (pin "28") (pinfunction "GND_28") (pintype "bidirectional"))
    )
    (net (code "112") (name "unconnected-(COPERNICUS_II-LNA-Pad5)") (class "Default")
      (node (ref "COPERNICUS_II") (pin "5") (pinfunction "LNA_5") (pintype "bidirectional"))
    )
    (net (code "113") (name "unconnected-(COPERNICUS_II-OPEN-Pad7)") (class "Default")
      (node (ref "COPERNICUS_II") (pin "7") (pinfunction "OPEN_7") (pintype "bidirectional"))
    )
    (net (code "114") (name "unconnected-(COPERNICUS_II-PPS-Pad19)") (class "Default")
      (node (ref "COPERNICUS_II") (pin "19") (pinfunction "PPS_19") (pintype "bidirectional"))
    )
    (net (code "115") (name "unconnected-(COPERNICUS_II-RESERVED1-Pad6)") (class "Default")
      (node (ref "COPERNICUS_II") (pin "6") (pinfunction "RESERVED1_6") (pintype "bidirectional"))
    )
    (net (code "116") (name "unconnected-(COPERNICUS_II-RESERVED3-Pad17)") (class "Default")
      (node (ref "COPERNICUS_II") (pin "17") (pinfunction "RESERVED3_17") (pintype "bidirectional"))
    )
    (net (code "117") (name "unconnected-(COPERNICUS_II-RESERVED4-Pad18)") (class "Default")
      (node (ref "COPERNICUS_II") (pin "18") (pinfunction "RESERVED4_18") (pintype "bidirectional"))
    )
    (net (code "118") (name "unconnected-(COPERNICUS_II-RESERVED5-Pad22)") (class "Default")
      (node (ref "COPERNICUS_II") (pin "22") (pinfunction "RESERVED5_22") (pintype "bidirectional"))
    )
    (net (code "119") (name "unconnected-(COPERNICUS_II-RESERVED6-Pad25)") (class "Default")
      (node (ref "COPERNICUS_II") (pin "25") (pinfunction "RESERVED6_25") (pintype "bidirectional"))
    )
    (net (code "120") (name "unconnected-(COPERNICUS_II-RESERVED7-Pad26)") (class "Default")
      (node (ref "COPERNICUS_II") (pin "26") (pinfunction "RESERVED7_26") (pintype "bidirectional"))
    )
    (net (code "121") (name "unconnected-(COPERNICUS_II-RFIN-Pad3)") (class "Default")
      (node (ref "COPERNICUS_II") (pin "3") (pinfunction "RFIN_3") (pintype "bidirectional"))
    )
    (net (code "122") (name "unconnected-(COPERNICUS_II-RXD-A-Pad21)") (class "Default")
      (node (ref "COPERNICUS_II") (pin "21") (pinfunction "RXD-A_21") (pintype "bidirectional"))
    )
    (net (code "123") (name "unconnected-(COPERNICUS_II-SHORT-Pad8)") (class "Default")
      (node (ref "COPERNICUS_II") (pin "8") (pinfunction "SHORT_8") (pintype "bidirectional"))
    )
    (net (code "124") (name "unconnected-(COPERNICUS_II-TXD-A-Pad23)") (class "Default")
      (node (ref "COPERNICUS_II") (pin "23") (pinfunction "TXD-A_23") (pintype "bidirectional"))
    )
    (net (code "125") (name "unconnected-(COPERNICUS_II-XRESET-Pad11)") (class "Default")
      (node (ref "COPERNICUS_II") (pin "11") (pinfunction "XRESET_11") (pintype "bidirectional"))
    )
    (net (code "126") (name "unconnected-(COPERNICUS_II-XSTANDBY-Pad16)") (class "Default")
      (node (ref "COPERNICUS_II") (pin "16") (pinfunction "XSTANDBY_16") (pintype "bidirectional"))
    )
    (net (code "127") (name "unconnected-(OPC_HEATER_RELAY-2-Pad3)") (class "Default")
      (node (ref "OPC_HEATER_RELAY") (pin "3") (pinfunction "2_3") (pintype "passive"))
    )
    (net (code "128") (name "unconnected-(OPC_HEATER_RELAY-3-Pad4)") (class "Default")
      (node (ref "OPC_HEATER_RELAY") (pin "4") (pinfunction "3_4") (pintype "passive"))
    )
    (net (code "129") (name "unconnected-(OPC_HEATER_RELAY-4-Pad5)") (class "Default")
      (node (ref "OPC_HEATER_RELAY") (pin "5") (pinfunction "4_5") (pintype "passive"))
    )
    (net (code "130") (name "unconnected-(OPC_HEATER_RELAY-9-Pad10)") (class "Default")
      (node (ref "OPC_HEATER_RELAY") (pin "10") (pinfunction "9_10") (pintype "passive"))
    )
    (net (code "131") (name "unconnected-(OPC_RELAY-2-Pad3)") (class "Default")
      (node (ref "OPC_RELAY") (pin "3") (pinfunction "2_3") (pintype "passive"))
    )
    (net (code "132") (name "unconnected-(OPC_RELAY-3-Pad4)") (class "Default")
      (node (ref "OPC_RELAY") (pin "4") (pinfunction "3_4") (pintype "passive"))
    )
    (net (code "133") (name "unconnected-(OPC_RELAY-4-Pad5)") (class "Default")
      (node (ref "OPC_RELAY") (pin "5") (pinfunction "4_5") (pintype "passive"))
    )
    (net (code "134") (name "unconnected-(OPC_RELAY-9-Pad10)") (class "Default")
      (node (ref "OPC_RELAY") (pin "10") (pinfunction "9_10") (pintype "passive"))
    )
    (net (code "135") (name "unconnected-(U1-NC-Pad3)") (class "Default")
      (node (ref "U1") (pin "3") (pinfunction "NC_3") (pintype "bidirectional"))
    )
    (net (code "136") (name "unconnected-(U1-N{slash}C-Pad11)") (class "Default")
      (node (ref "U1") (pin "11") (pinfunction "N/C_11") (pintype "bidirectional"))
    )
  )
)
